# Sch2.net
KiCad netlist of a schematic drawn in Altium Designer
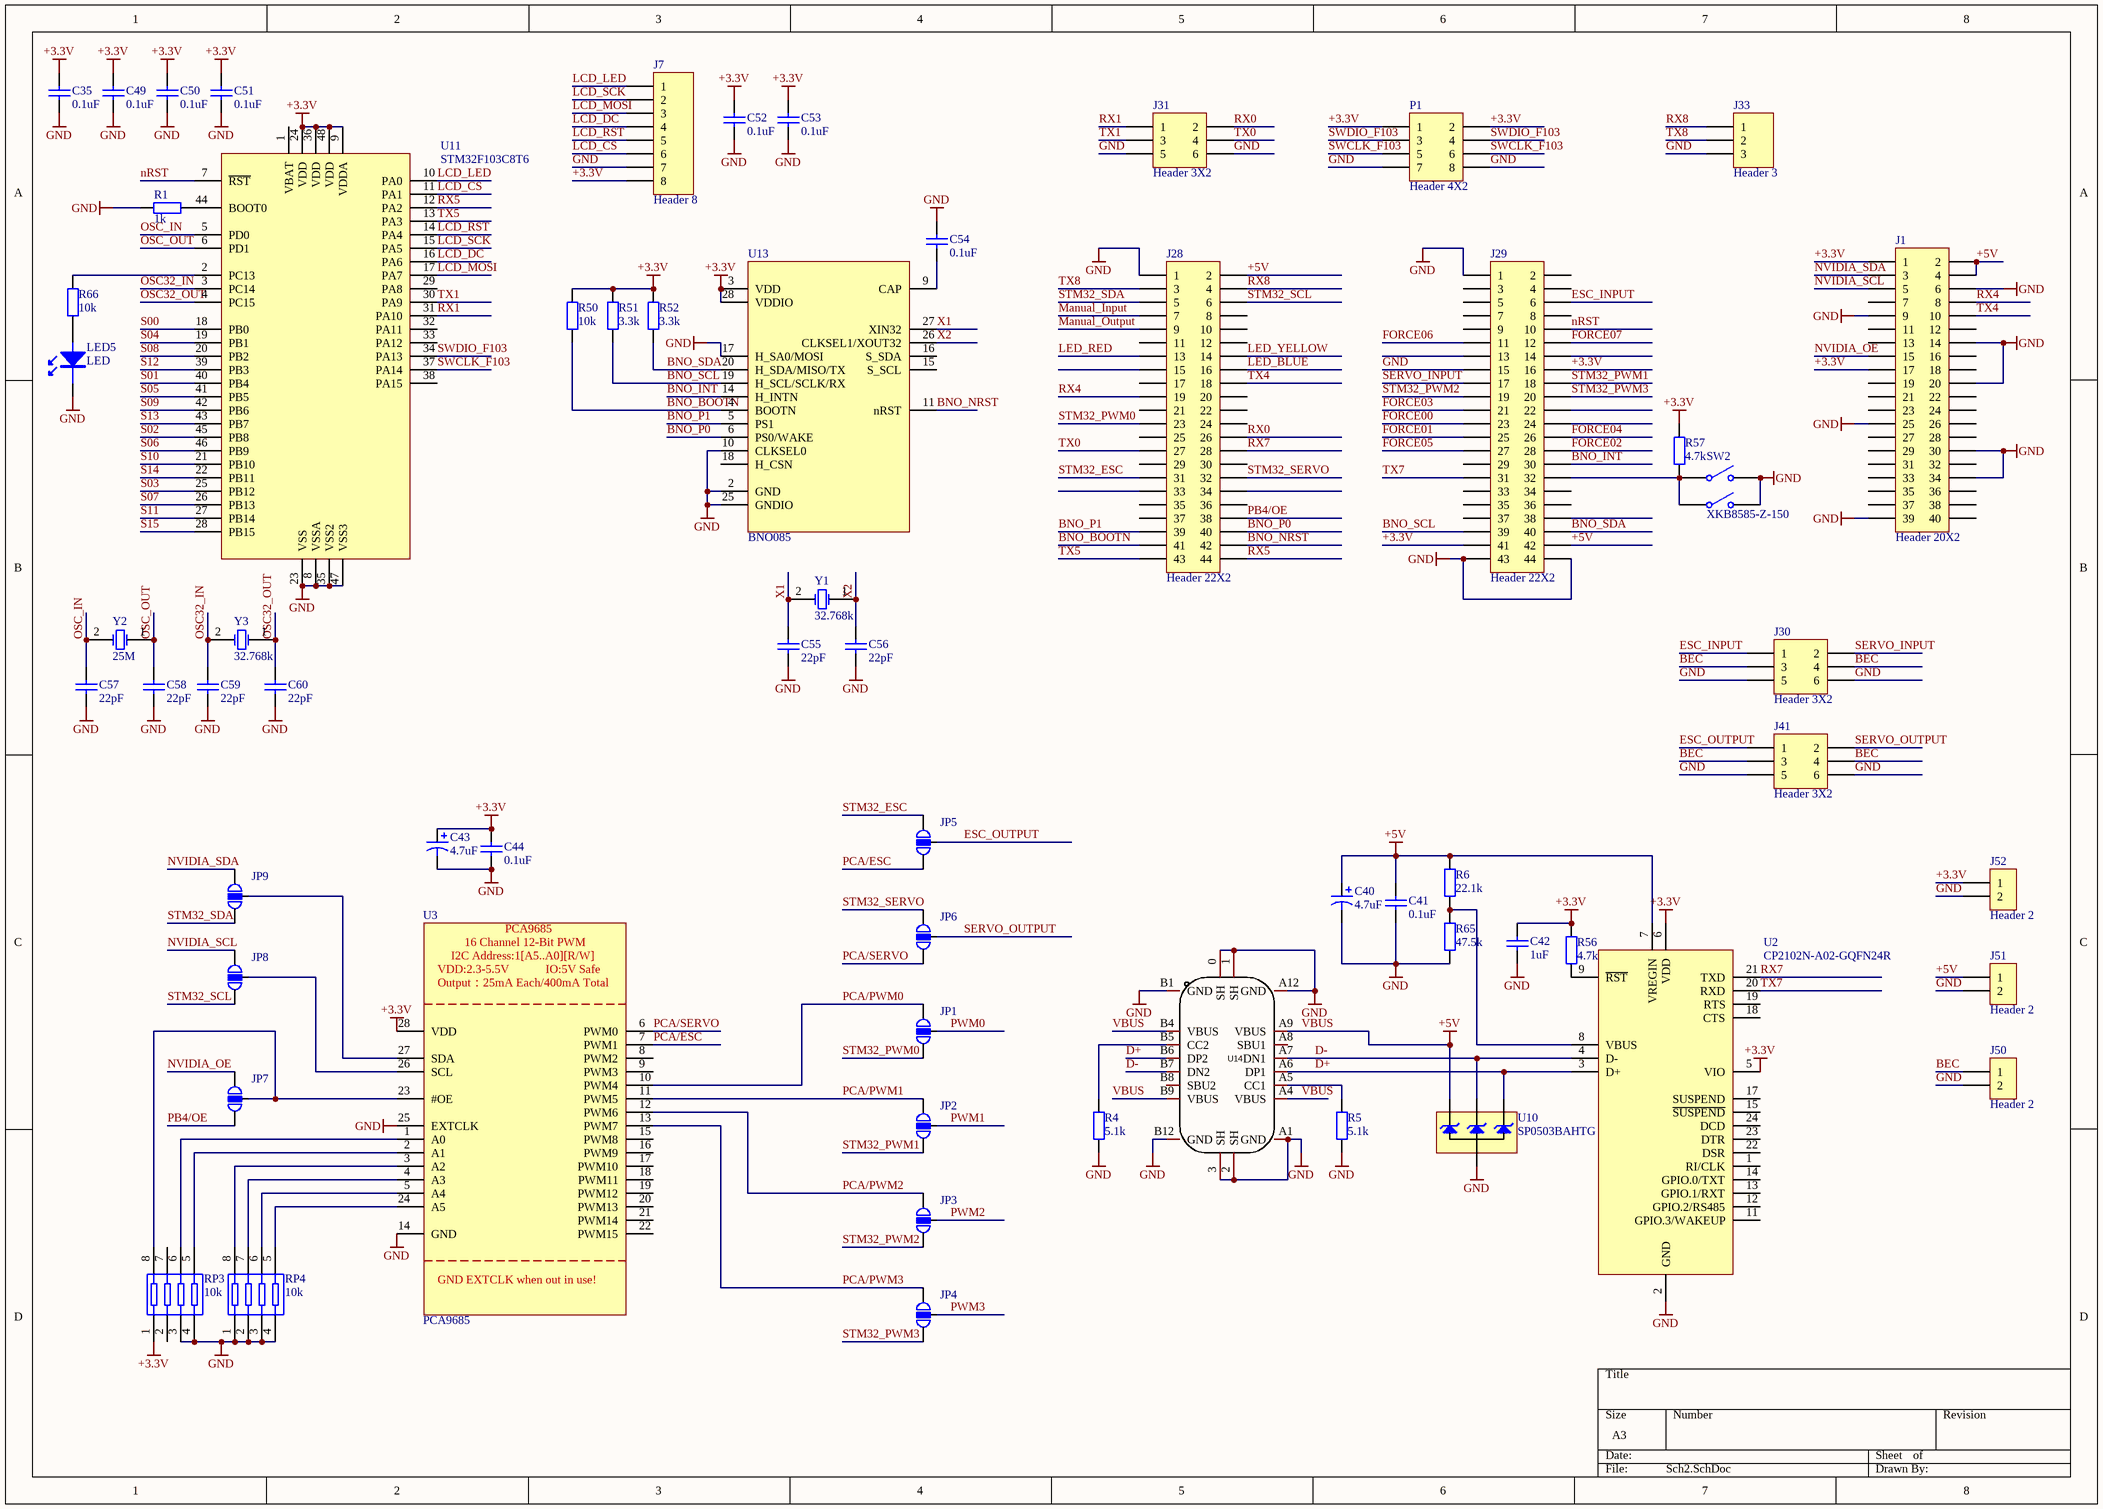
[diagram p0: Sch2.SchDoc]

(export (version "E")
  (design (tool "Eeschema 10.0.6"))
  (components
    (comp (ref "C35")
      (value "0.1uF")
      (footprint "CC0603")
      (description "贴片电容")
      (fields (field (name "Comment") "0603-50V-0.1uF"))
      (libsource (lib "Miscellaneous Devices") (part "Cap"))
    )
    (comp (ref "C40")
      (value "4.7uF")
      (footprint "SMD-EC-F5")
      (description "贴片铝电解电容")
      (fields (field (name "Comment") "CD-50V-4.7uF-F5(SMD)"))
      (libsource (lib "Miscellaneous Devices") (part "Cap Pol1"))
    )
    (comp (ref "C41")
      (value "0.1uF")
      (footprint "CC0603")
      (description "贴片电容")
      (fields (field (name "Comment") "0603-50V-0.1uF"))
      (libsource (lib "Miscellaneous Devices") (part "Cap"))
    )
    (comp (ref "C42")
      (value "1uF")
      (footprint "CC0603")
      (description "贴片电容")
      (fields (field (name "Comment") "0603-50V-1uF"))
      (libsource (lib "Miscellaneous Devices") (part "Cap"))
    )
    (comp (ref "C43")
      (value "4.7uF")
      (footprint "SMD-EC-F5")
      (description "贴片铝电解电容")
      (fields (field (name "Comment") "CD-50V-4.7uF-F5(SMD)"))
      (libsource (lib "Miscellaneous Devices") (part "Cap Pol1"))
    )
    (comp (ref "C44")
      (value "0.1uF")
      (footprint "CC0603")
      (description "贴片电容")
      (fields (field (name "Comment") "0603-50V-0.1uF"))
      (libsource (lib "Miscellaneous Devices") (part "Cap"))
    )
    (comp (ref "C49")
      (value "0.1uF")
      (footprint "CC0603")
      (description "贴片电容")
      (fields (field (name "Comment") "0603-50V-0.1uF"))
      (libsource (lib "Miscellaneous Devices") (part "Cap"))
    )
    (comp (ref "C50")
      (value "0.1uF")
      (footprint "CC0603")
      (description "贴片电容")
      (fields (field (name "Comment") "0603-50V-0.1uF"))
      (libsource (lib "Miscellaneous Devices") (part "Cap"))
    )
    (comp (ref "C51")
      (value "0.1uF")
      (footprint "CC0603")
      (description "贴片电容")
      (fields (field (name "Comment") "0603-50V-0.1uF"))
      (libsource (lib "Miscellaneous Devices") (part "Cap"))
    )
    (comp (ref "C52")
      (value "0.1uF")
      (footprint "CC0603")
      (description "贴片电容")
      (fields (field (name "Comment") "0603-50V-0.1uF"))
      (libsource (lib "Miscellaneous Devices") (part "Cap"))
    )
    (comp (ref "C53")
      (value "0.1uF")
      (footprint "CC0603")
      (description "贴片电容")
      (fields (field (name "Comment") "0603-50V-0.1uF"))
      (libsource (lib "Miscellaneous Devices") (part "Cap"))
    )
    (comp (ref "C54")
      (value "0.1uF")
      (footprint "CC0603")
      (description "贴片电容")
      (fields (field (name "Comment") "0603-50V-0.1uF"))
      (libsource (lib "Miscellaneous Devices") (part "Cap"))
    )
    (comp (ref "C55")
      (value "22pF")
      (footprint "CC0603")
      (description "贴片电容")
      (fields (field (name "Comment") "0603-50V-22pF"))
      (libsource (lib "Miscellaneous Devices") (part "Cap"))
    )
    (comp (ref "C56")
      (value "22pF")
      (footprint "CC0603")
      (description "贴片电容")
      (fields (field (name "Comment") "0603-50V-22pF"))
      (libsource (lib "Miscellaneous Devices") (part "Cap"))
    )
    (comp (ref "C57")
      (value "22pF")
      (footprint "CC0603")
      (description "贴片电容")
      (fields (field (name "Comment") "0603-50V-22pF"))
      (libsource (lib "Miscellaneous Devices") (part "Cap"))
    )
    (comp (ref "C58")
      (value "22pF")
      (footprint "CC0603")
      (description "贴片电容")
      (fields (field (name "Comment") "0603-50V-22pF"))
      (libsource (lib "Miscellaneous Devices") (part "Cap"))
    )
    (comp (ref "C59")
      (value "22pF")
      (footprint "CC0603")
      (description "贴片电容")
      (fields (field (name "Comment") "0603-50V-22pF"))
      (libsource (lib "Miscellaneous Devices") (part "Cap"))
    )
    (comp (ref "C60")
      (value "22pF")
      (footprint "CC0603")
      (description "贴片电容")
      (fields (field (name "Comment") "0603-50V-22pF"))
      (libsource (lib "Miscellaneous Devices") (part "Cap"))
    )
    (comp (ref "J1")
      (value "Header 20X2")
      (footprint "HDR2X20")
      (description "排针")
      (libsource (lib "Miscellaneous Connectors") (part "Header 20X2"))
    )
    (comp (ref "J7")
      (value "Header 8")
      (footprint "HDR1X8")
      (description "排针")
      (libsource (lib "Miscellaneous Connectors") (part "Header 8"))
    )
    (comp (ref "J28")
      (value "Header 22X2")
      (footprint "HDR2X22")
      (description "排针")
      (libsource (lib "Miscellaneous Connectors") (part "Header 22X2"))
    )
    (comp (ref "J29")
      (value "Header 22X2")
      (footprint "HDR2X22")
      (description "排针")
      (libsource (lib "Miscellaneous Connectors") (part "Header 22X2"))
    )
    (comp (ref "J30")
      (value "Header 3X2")
      (footprint "HDR2X3")
      (description "排针")
      (libsource (lib "Miscellaneous Connectors") (part "Header 3X2"))
    )
    (comp (ref "J31")
      (value "Header 3X2")
      (footprint "HDR2X3")
      (description "排针")
      (libsource (lib "Miscellaneous Connectors") (part "Header 3X2"))
    )
    (comp (ref "J33")
      (value "Header 3")
      (footprint "HDR1X3")
      (description "排针")
      (libsource (lib "Miscellaneous Connectors") (part "Header 3"))
    )
    (comp (ref "J41")
      (value "Header 3X2")
      (footprint "HDR2X3")
      (description "排针")
      (libsource (lib "Miscellaneous Connectors") (part "Header 3X2"))
    )
    (comp (ref "J50")
      (value "Header 2")
      (footprint "HDR1X2")
      (description "排针")
      (libsource (lib "*") (part "CON2"))
    )
    (comp (ref "J51")
      (value "Header 2")
      (footprint "HDR1X2")
      (description "排针")
      (libsource (lib "*") (part "CON2"))
    )
    (comp (ref "J52")
      (value "Header 2")
      (footprint "HDR1X2")
      (description "排针")
      (libsource (lib "*") (part "CON2"))
    )
    (comp (ref "JP1") (value "Jumper") (footprint "HDR1X3") (libsource (lib "SHIELD_3") (part "Bell")))
    (comp (ref "JP2") (value "Jumper") (footprint "HDR1X3") (libsource (lib "SHIELD_3") (part "Bell")))
    (comp (ref "JP3") (value "Jumper") (footprint "HDR1X3") (libsource (lib "SHIELD_3") (part "Bell")))
    (comp (ref "JP4") (value "Jumper") (footprint "HDR1X3") (libsource (lib "SHIELD_3") (part "Bell")))
    (comp (ref "JP5") (value "Jumper") (footprint "HDR1X3") (libsource (lib "SHIELD_3") (part "Bell")))
    (comp (ref "JP6") (value "Jumper") (footprint "HDR1X3") (libsource (lib "SHIELD_3") (part "Bell")))
    (comp (ref "JP7") (value "Jumper") (footprint "HDR1X3") (libsource (lib "SHIELD_3") (part "Bell")))
    (comp (ref "JP8") (value "Jumper") (footprint "HDR1X3") (libsource (lib "SHIELD_3") (part "Bell")))
    (comp (ref "JP9") (value "Jumper") (footprint "HDR1X3") (libsource (lib "SHIELD_3") (part "Bell")))
    (comp (ref "LED5")
      (value "LED")
      (footprint "LED0603")
      (description "发光二极管")
      (fields (field (name "Comment") "0603-LED-(蓝)"))
      (libsource (lib "*") (part "LED"))
    )
    (comp (ref "P1")
      (value "Header 4X2")
      (footprint "HDR2X4")
      (description "排针")
      (libsource (lib "Miscellaneous Connectors") (part "Header 4X2"))
    )
    (comp (ref "R1")
      (value "1k")
      (footprint "0603")
      (description "贴片电阻")
      (fields (field (name "Comment") "0603-1kΩ±1％"))
      (libsource (lib "") (part "Res2_2"))
    )
    (comp (ref "R4")
      (value "5.1k")
      (footprint "0603")
      (description "贴片电阻")
      (fields (field (name "Comment") "0603-5.1kΩ±1％"))
      (libsource (lib "") (part "Res2_1"))
    )
    (comp (ref "R5")
      (value "5.1k")
      (footprint "0603")
      (description "贴片电阻")
      (fields (field (name "Comment") "0603-5.1kΩ±1％"))
      (libsource (lib "") (part "Res2_1"))
    )
    (comp (ref "R6")
      (value "22.1k")
      (footprint "0603")
      (description "贴片电阻")
      (fields (field (name "Comment") "0603-22.1kΩ±1％"))
      (libsource (lib "Miscellaneous Devices") (part "Res2"))
    )
    (comp (ref "R50")
      (value "10k")
      (footprint "0603")
      (description "贴片电阻")
      (fields (field (name "Comment") "0603-10kΩ±1％"))
      (libsource (lib "") (part "Res2_1"))
    )
    (comp (ref "R51")
      (value "3.3k")
      (footprint "0603")
      (description "贴片电阻")
      (fields (field (name "Comment") "0603-3.3kΩ±1％"))
      (libsource (lib "") (part "Res2_1"))
    )
    (comp (ref "R52")
      (value "3.3k")
      (footprint "0603")
      (description "贴片电阻")
      (fields (field (name "Comment") "0603-3.3kΩ±1％"))
      (libsource (lib "") (part "Res2_1"))
    )
    (comp (ref "R56")
      (value "4.7k")
      (footprint "0603")
      (description "贴片电阻")
      (fields (field (name "Comment") "0603-4.7kΩ±1％"))
      (libsource (lib "Miscellaneous Devices") (part "Res2"))
    )
    (comp (ref "R57")
      (value "4.7k")
      (footprint "0603")
      (description "贴片电阻")
      (fields (field (name "Comment") "0603-4.7kΩ±1％"))
      (libsource (lib "Miscellaneous Devices") (part "Res2"))
    )
    (comp (ref "R65")
      (value "47.5k")
      (footprint "0603")
      (description "贴片电阻")
      (fields (field (name "Comment") "0603-47.5kΩ±1％"))
      (libsource (lib "Miscellaneous Devices") (part "Res2"))
    )
    (comp (ref "R66")
      (value "10k")
      (footprint "0603")
      (description "贴片电阻")
      (fields (field (name "Comment") "0603-10kΩ±1％"))
      (libsource (lib "") (part "Res2_1"))
    )
    (comp (ref "RP3")
      (value "10k")
      (footprint "RP8F")
      (description "排阻")
      (fields (field (name "Comment") "0603-10kΩ-2*4P"))
      (libsource (lib "*") (part "RESPACK8P"))
    )
    (comp (ref "RP4")
      (value "10k")
      (footprint "RP8F")
      (description "排阻")
      (fields (field (name "Comment") "0603-10kΩ-2*4P"))
      (libsource (lib "*") (part "RESPACK8P"))
    )
    (comp (ref "SW2")
      (value "XKB8585-Z-150")
      (footprint "KEY_SWITCH")
      (description "开关")
      (libsource (lib "PCB_Project") (part "SW-SPST"))
    )
    (comp (ref "U2")
      (value "CP2102N-A02-GQFN24R")
      (footprint "QFN24")
      (description "集成电路")
      (libsource (lib "PCB_Project") (part "CP2102N-A02-GQFN24R"))
    )
    (comp (ref "U3")
      (value "PCA9685")
      (footprint "LYDZ:TSSOP-28")
      (description "集成电路")
      (libsource (lib "Schlib1") (part "PCA9685"))
    )
    (comp (ref "U10")
      (value "SP0503BAHTG")
      (footprint "SOT143-4")
      (description "集成电路")
      (libsource (lib "PCB_Project") (part "SP0503BAHTG"))
    )
    (comp (ref "U11")
      (value "STM32F103C8T6")
      (footprint "LQFP48")
      (description "集成电路")
      (libsource (lib "Schlib2") (part "STM32F103C8T6"))
    )
    (comp (ref "U13")
      (value "BNO085")
      (footprint "LGA28")
      (description "集成电路")
      (libsource (lib "Schlib1") (part "BNO080"))
    )
    (comp (ref "U14")
      (value "TYPE-C-31-M-12")
      (footprint "USB-C_SMD-TYPE-C-31-M-12")
      (fields (field (name "MANUFACTURER") "韩国韩荣"))
      (libsource (lib "altium-import") (part "root_0_TYPE-C-31-M-12_"))
    )
    (comp (ref "Y1")
      (value "32.768k")
      (footprint "XTAL-FA135")
      (description "Crystal Oscillator")
      (fields (field (name "PUBLISHER") "Altium Limited"))
      (libsource (lib "Miscellaneous Devices") (part "XTAL"))
    )
    (comp (ref "Y2")
      (value "25M")
      (footprint "XT49M")
      (description "Crystal Oscillator")
      (fields (field (name "PUBLISHER") "Altium Limited"))
      (libsource (lib "Miscellaneous Devices") (part "XTAL"))
    )
    (comp (ref "Y3")
      (value "32.768k")
      (footprint "XTAL-FA135")
      (description "Crystal Oscillator")
      (fields (field (name "PUBLISHER") "Altium Limited"))
      (libsource (lib "Miscellaneous Devices") (part "XTAL"))
    )
  )
  (nets
    (net (code "1") (name "+3.3V") (class "Default")
      (node (ref "C35") (pin "2") (pinfunction "2_2") (pintype "passive"))
      (node (ref "C42") (pin "2") (pinfunction "2_2") (pintype "passive"))
      (node (ref "C43") (pin "1") (pinfunction "1_1") (pintype "passive"))
      (node (ref "C44") (pin "2") (pinfunction "2_2") (pintype "passive"))
      (node (ref "C49") (pin "2") (pinfunction "2_2") (pintype "passive"))
      (node (ref "C50") (pin "2") (pinfunction "2_2") (pintype "passive"))
      (node (ref "C51") (pin "2") (pinfunction "2_2") (pintype "passive"))
      (node (ref "C52") (pin "2") (pinfunction "2_2") (pintype "passive"))
      (node (ref "C53") (pin "2") (pinfunction "2_2") (pintype "passive"))
      (node (ref "J1") (pin "1") (pinfunction "1_1") (pintype "passive"))
      (node (ref "J1") (pin "17") (pinfunction "17_17") (pintype "passive"))
      (node (ref "J29") (pin "16") (pinfunction "16_16") (pintype "passive"))
      (node (ref "J29") (pin "41") (pinfunction "41_41") (pintype "passive"))
      (node (ref "J52") (pin "1") (pinfunction "1_1") (pintype "passive"))
      (node (ref "J7") (pin "8") (pinfunction "8_8") (pintype "passive"))
      (node (ref "P1") (pin "1") (pinfunction "1_1") (pintype "passive"))
      (node (ref "P1") (pin "2") (pinfunction "2_2") (pintype "passive"))
      (node (ref "R50") (pin "2") (pinfunction "2_2") (pintype "passive"))
      (node (ref "R51") (pin "2") (pinfunction "2_2") (pintype "passive"))
      (node (ref "R52") (pin "2") (pinfunction "2_2") (pintype "passive"))
      (node (ref "R56") (pin "1") (pinfunction "1_1") (pintype "passive"))
      (node (ref "R57") (pin "1") (pinfunction "1_1") (pintype "passive"))
      (node (ref "RP3") (pin "1") (pinfunction "1_1") (pintype "passive"))
      (node (ref "U11") (pin "24") (pinfunction "VDD_24") (pintype "passive"))
      (node (ref "U11") (pin "36") (pinfunction "VDD_36") (pintype "passive"))
      (node (ref "U11") (pin "48") (pinfunction "VDD_48") (pintype "passive"))
      (node (ref "U11") (pin "9") (pinfunction "VDDA_9") (pintype "passive"))
      (node (ref "U13") (pin "28") (pinfunction "VDDIO_28") (pintype "passive"))
      (node (ref "U13") (pin "3") (pinfunction "VDD_3") (pintype "passive"))
      (node (ref "U2") (pin "5") (pinfunction "VIO_5") (pintype "passive"))
      (node (ref "U2") (pin "6") (pinfunction "VDD_6") (pintype "passive"))
      (node (ref "U3") (pin "28") (pinfunction "VDD_28") (pintype "passive"))
    )
    (net (code "2") (name "+5V") (class "Default")
      (node (ref "C40") (pin "1") (pinfunction "1_1") (pintype "passive"))
      (node (ref "C41") (pin "2") (pinfunction "2_2") (pintype "passive"))
      (node (ref "J1") (pin "2") (pinfunction "2_2") (pintype "passive"))
      (node (ref "J1") (pin "4") (pinfunction "4_4") (pintype "passive"))
      (node (ref "J28") (pin "2") (pinfunction "2_2") (pintype "passive"))
      (node (ref "J29") (pin "42") (pinfunction "42_42") (pintype "passive"))
      (node (ref "J51") (pin "1") (pinfunction "1_1") (pintype "passive"))
      (node (ref "R6") (pin "1") (pinfunction "1_1") (pintype "passive"))
      (node (ref "U10") (pin "2") (pinfunction "K_2") (pintype "passive"))
      (node (ref "U14") (pin "A4") (pinfunction "VBUS_A4") (pintype "passive"))
      (node (ref "U14") (pin "A9") (pinfunction "VBUS_A9") (pintype "passive"))
      (node (ref "U14") (pin "B4") (pinfunction "VBUS_B4") (pintype "passive"))
      (node (ref "U14") (pin "B9") (pinfunction "VBUS_B9") (pintype "passive"))
      (node (ref "U2") (pin "7") (pinfunction "VREGIN_7") (pintype "passive"))
    )
    (net (code "3") (name "/BEC") (class "Default")
      (node (ref "J30") (pin "3") (pinfunction "3_3") (pintype "passive"))
      (node (ref "J30") (pin "4") (pinfunction "4_4") (pintype "passive"))
      (node (ref "J41") (pin "3") (pinfunction "3_3") (pintype "passive"))
      (node (ref "J41") (pin "4") (pinfunction "4_4") (pintype "passive"))
      (node (ref "J50") (pin "1") (pinfunction "1_1") (pintype "passive"))
    )
    (net (code "4") (name "/BNO_BOOTN") (class "Default")
      (node (ref "J28") (pin "41") (pinfunction "41_41") (pintype "passive"))
      (node (ref "R50") (pin "1") (pinfunction "1_1") (pintype "passive"))
      (node (ref "U13") (pin "4") (pinfunction "BOOTN_4") (pintype "passive"))
    )
    (net (code "5") (name "/BNO_INT") (class "Default")
      (node (ref "J29") (pin "30") (pinfunction "30_30") (pintype "passive"))
      (node (ref "U13") (pin "14") (pinfunction "H_INTN_14") (pintype "passive"))
    )
    (net (code "6") (name "/BNO_NRST") (class "Default")
      (node (ref "J28") (pin "42") (pinfunction "42_42") (pintype "passive"))
      (node (ref "U13") (pin "11") (pinfunction "nRST_11") (pintype "passive"))
    )
    (net (code "7") (name "/BNO_P0") (class "Default")
      (node (ref "J28") (pin "40") (pinfunction "40_40") (pintype "passive"))
      (node (ref "U13") (pin "6") (pinfunction "PS0/WAKE_6") (pintype "passive"))
    )
    (net (code "8") (name "/BNO_P1") (class "Default")
      (node (ref "J28") (pin "39") (pinfunction "39_39") (pintype "passive"))
      (node (ref "U13") (pin "5") (pinfunction "PS1_5") (pintype "passive"))
    )
    (net (code "9") (name "/BNO_SCL") (class "Default")
      (node (ref "J29") (pin "39") (pinfunction "39_39") (pintype "passive"))
      (node (ref "R51") (pin "1") (pinfunction "1_1") (pintype "passive"))
      (node (ref "U13") (pin "19") (pinfunction "H_SCL/SCLK/RX_19") (pintype "passive"))
    )
    (net (code "10") (name "/BNO_SDA") (class "Default")
      (node (ref "J29") (pin "40") (pinfunction "40_40") (pintype "passive"))
      (node (ref "R52") (pin "1") (pinfunction "1_1") (pintype "passive"))
      (node (ref "U13") (pin "20") (pinfunction "H_SDA/MISO/TX_20") (pintype "passive"))
    )
    (net (code "11") (name "/D+") (class "Default")
      (node (ref "U10") (pin "4") (pinfunction "K_4") (pintype "passive"))
      (node (ref "U14") (pin "A6") (pinfunction "DP1_A6") (pintype "passive"))
      (node (ref "U14") (pin "B6") (pinfunction "DP2_B6") (pintype "passive"))
      (node (ref "U2") (pin "3") (pinfunction "D+_3") (pintype "passive"))
    )
    (net (code "12") (name "/D-") (class "Default")
      (node (ref "U10") (pin "3") (pinfunction "K_3") (pintype "passive"))
      (node (ref "U14") (pin "A7") (pinfunction "DN1_A7") (pintype "passive"))
      (node (ref "U14") (pin "B7") (pinfunction "DN2_B7") (pintype "passive"))
      (node (ref "U2") (pin "4") (pinfunction "D-_4") (pintype "passive"))
    )
    (net (code "13") (name "/ESC_INPUT") (class "Default")
      (node (ref "J29") (pin "6") (pinfunction "6_6") (pintype "passive"))
      (node (ref "J30") (pin "1") (pinfunction "1_1") (pintype "passive"))
    )
    (net (code "14") (name "/ESC_OUTPUT") (class "Default")
      (node (ref "J41") (pin "1") (pinfunction "1_1") (pintype "passive"))
      (node (ref "JP5") (pin "2") (pinfunction "B_2") (pintype "passive"))
    )
    (net (code "15") (name "/FORCE00") (class "Default")
      (node (ref "J29") (pin "23") (pinfunction "23_23") (pintype "passive"))
    )
    (net (code "16") (name "/FORCE01") (class "Default")
      (node (ref "J29") (pin "25") (pinfunction "25_25") (pintype "passive"))
    )
    (net (code "17") (name "/FORCE02") (class "Default")
      (node (ref "J29") (pin "28") (pinfunction "28_28") (pintype "passive"))
    )
    (net (code "18") (name "/FORCE03") (class "Default")
      (node (ref "J29") (pin "21") (pinfunction "21_21") (pintype "passive"))
    )
    (net (code "19") (name "/FORCE04") (class "Default")
      (node (ref "J29") (pin "26") (pinfunction "26_26") (pintype "passive"))
    )
    (net (code "20") (name "/FORCE05") (class "Default")
      (node (ref "J29") (pin "27") (pinfunction "27_27") (pintype "passive"))
    )
    (net (code "21") (name "/FORCE06") (class "Default")
      (node (ref "J29") (pin "11") (pinfunction "11_11") (pintype "passive"))
    )
    (net (code "22") (name "/FORCE07") (class "Default")
      (node (ref "J29") (pin "12") (pinfunction "12_12") (pintype "passive"))
    )
    (net (code "23") (name "/LCD_CS") (class "Default")
      (node (ref "J7") (pin "6") (pinfunction "6_6") (pintype "passive"))
      (node (ref "U11") (pin "11") (pinfunction "PA1_11") (pintype "passive"))
    )
    (net (code "24") (name "/LCD_DC") (class "Default")
      (node (ref "J7") (pin "4") (pinfunction "4_4") (pintype "passive"))
      (node (ref "U11") (pin "16") (pinfunction "PA6_16") (pintype "passive"))
    )
    (net (code "25") (name "/LCD_LED") (class "Default")
      (node (ref "J7") (pin "1") (pinfunction "1_1") (pintype "passive"))
      (node (ref "U11") (pin "10") (pinfunction "PA0_10") (pintype "passive"))
    )
    (net (code "26") (name "/LCD_MOSI") (class "Default")
      (node (ref "J7") (pin "3") (pinfunction "3_3") (pintype "passive"))
      (node (ref "U11") (pin "17") (pinfunction "PA7_17") (pintype "passive"))
    )
    (net (code "27") (name "/LCD_RST") (class "Default")
      (node (ref "J7") (pin "5") (pinfunction "5_5") (pintype "passive"))
      (node (ref "U11") (pin "14") (pinfunction "PA4_14") (pintype "passive"))
    )
    (net (code "28") (name "/LCD_SCK") (class "Default")
      (node (ref "J7") (pin "2") (pinfunction "2_2") (pintype "passive"))
      (node (ref "U11") (pin "15") (pinfunction "PA5_15") (pintype "passive"))
    )
    (net (code "29") (name "/LED_BLUE") (class "Default")
      (node (ref "J28") (pin "16") (pinfunction "16_16") (pintype "passive"))
    )
    (net (code "30") (name "/LED_RED") (class "Default")
      (node (ref "J28") (pin "13") (pinfunction "13_13") (pintype "passive"))
    )
    (net (code "31") (name "/LED_YELLOW") (class "Default")
      (node (ref "J28") (pin "14") (pinfunction "14_14") (pintype "passive"))
    )
    (net (code "32") (name "/Manual_Input") (class "Default")
      (node (ref "J28") (pin "7") (pinfunction "7_7") (pintype "passive"))
    )
    (net (code "33") (name "/Manual_Output") (class "Default")
      (node (ref "J28") (pin "9") (pinfunction "9_9") (pintype "passive"))
    )
    (net (code "34") (name "/NVIDIA_OE") (class "Default")
      (node (ref "J1") (pin "15") (pinfunction "15_15") (pintype "passive"))
      (node (ref "JP7") (pin "1") (pinfunction "A_1") (pintype "passive"))
    )
    (net (code "35") (name "/NVIDIA_SCL") (class "Default")
      (node (ref "J1") (pin "5") (pinfunction "5_5") (pintype "passive"))
      (node (ref "JP8") (pin "1") (pinfunction "A_1") (pintype "passive"))
    )
    (net (code "36") (name "/NVIDIA_SDA") (class "Default")
      (node (ref "J1") (pin "3") (pinfunction "3_3") (pintype "passive"))
      (node (ref "JP9") (pin "1") (pinfunction "A_1") (pintype "passive"))
    )
    (net (code "37") (name "/OSC32_IN") (class "Default")
      (node (ref "C59") (pin "1") (pinfunction "1_1") (pintype "passive"))
      (node (ref "U11") (pin "3") (pinfunction "PC14_3") (pintype "passive"))
      (node (ref "Y3") (pin "2") (pinfunction "OSC2_2") (pintype "passive"))
    )
    (net (code "38") (name "/OSC32_OUT") (class "Default")
      (node (ref "C60") (pin "1") (pinfunction "1_1") (pintype "passive"))
      (node (ref "U11") (pin "4") (pinfunction "PC15_4") (pintype "passive"))
      (node (ref "Y3") (pin "1") (pinfunction "OSC1_1") (pintype "passive"))
    )
    (net (code "39") (name "/OSC_IN") (class "Default")
      (node (ref "C57") (pin "1") (pinfunction "1_1") (pintype "passive"))
      (node (ref "U11") (pin "5") (pinfunction "PD0_5") (pintype "passive"))
      (node (ref "Y2") (pin "2") (pinfunction "OSC2_2") (pintype "passive"))
    )
    (net (code "40") (name "/OSC_OUT") (class "Default")
      (node (ref "C58") (pin "1") (pinfunction "1_1") (pintype "passive"))
      (node (ref "U11") (pin "6") (pinfunction "PD1_6") (pintype "passive"))
      (node (ref "Y2") (pin "1") (pinfunction "OSC1_1") (pintype "passive"))
    )
    (net (code "41") (name "/PB4{slash}OE") (class "Default")
      (node (ref "J28") (pin "38") (pinfunction "38_38") (pintype "passive"))
      (node (ref "JP7") (pin "3") (pinfunction "B_3") (pintype "passive"))
    )
    (net (code "42") (name "/PCA{slash}ESC") (class "Default")
      (node (ref "JP5") (pin "3") (pinfunction "B_3") (pintype "passive"))
      (node (ref "U3") (pin "7") (pinfunction "PWM1_7") (pintype "passive"))
    )
    (net (code "43") (name "/PCA{slash}PWM0") (class "Default")
      (node (ref "JP1") (pin "1") (pinfunction "A_1") (pintype "passive"))
      (node (ref "U3") (pin "10") (pinfunction "PWM4_10") (pintype "passive"))
    )
    (net (code "44") (name "/PCA{slash}PWM1") (class "Default")
      (node (ref "JP2") (pin "1") (pinfunction "A_1") (pintype "passive"))
      (node (ref "U3") (pin "11") (pinfunction "PWM5_11") (pintype "passive"))
    )
    (net (code "45") (name "/PCA{slash}PWM2") (class "Default")
      (node (ref "JP3") (pin "1") (pinfunction "A_1") (pintype "passive"))
      (node (ref "U3") (pin "12") (pinfunction "PWM6_12") (pintype "passive"))
    )
    (net (code "46") (name "/PCA{slash}PWM3") (class "Default")
      (node (ref "JP4") (pin "1") (pinfunction "A_1") (pintype "passive"))
      (node (ref "U3") (pin "13") (pinfunction "PWM7_13") (pintype "passive"))
    )
    (net (code "47") (name "/PCA{slash}SERVO") (class "Default")
      (node (ref "JP6") (pin "3") (pinfunction "B_3") (pintype "passive"))
      (node (ref "U3") (pin "6") (pinfunction "PWM0_6") (pintype "passive"))
    )
    (net (code "48") (name "/PWM0") (class "Default")
      (node (ref "JP1") (pin "2") (pinfunction "B_2") (pintype "passive"))
    )
    (net (code "49") (name "/PWM1") (class "Default")
      (node (ref "JP2") (pin "2") (pinfunction "B_2") (pintype "passive"))
    )
    (net (code "50") (name "/PWM2") (class "Default")
      (node (ref "JP3") (pin "2") (pinfunction "B_2") (pintype "passive"))
    )
    (net (code "51") (name "/PWM3") (class "Default")
      (node (ref "JP4") (pin "2") (pinfunction "B_2") (pintype "passive"))
    )
    (net (code "52") (name "/RX0") (class "Default")
      (node (ref "J28") (pin "26") (pinfunction "26_26") (pintype "passive"))
      (node (ref "J31") (pin "2") (pinfunction "2_2") (pintype "passive"))
    )
    (net (code "53") (name "/RX1") (class "Default")
      (node (ref "J31") (pin "1") (pinfunction "1_1") (pintype "passive"))
      (node (ref "U11") (pin "31") (pinfunction "PA10_31") (pintype "passive"))
    )
    (net (code "54") (name "/RX4") (class "Default")
      (node (ref "J1") (pin "8") (pinfunction "8_8") (pintype "passive"))
      (node (ref "J28") (pin "19") (pinfunction "19_19") (pintype "passive"))
    )
    (net (code "55") (name "/RX5") (class "Default")
      (node (ref "J28") (pin "44") (pinfunction "44_44") (pintype "passive"))
      (node (ref "U11") (pin "12") (pinfunction "PA2_12") (pintype "passive"))
    )
    (net (code "56") (name "/RX7") (class "Default")
      (node (ref "J28") (pin "28") (pinfunction "28_28") (pintype "passive"))
      (node (ref "U2") (pin "21") (pinfunction "TXD_21") (pintype "passive"))
    )
    (net (code "57") (name "/RX8") (class "Default")
      (node (ref "J28") (pin "4") (pinfunction "4_4") (pintype "passive"))
      (node (ref "J33") (pin "1") (pinfunction "1_1") (pintype "passive"))
    )
    (net (code "58") (name "/S00") (class "Default")
      (node (ref "U11") (pin "18") (pinfunction "PB0_18") (pintype "passive"))
    )
    (net (code "59") (name "/S01") (class "Default")
      (node (ref "U11") (pin "40") (pinfunction "PB4_40") (pintype "passive"))
    )
    (net (code "60") (name "/S02") (class "Default")
      (node (ref "U11") (pin "45") (pinfunction "PB8_45") (pintype "passive"))
    )
    (net (code "61") (name "/S03") (class "Default")
      (node (ref "U11") (pin "25") (pinfunction "PB12_25") (pintype "passive"))
    )
    (net (code "62") (name "/S04") (class "Default")
      (node (ref "U11") (pin "19") (pinfunction "PB1_19") (pintype "passive"))
    )
    (net (code "63") (name "/S05") (class "Default")
      (node (ref "U11") (pin "41") (pinfunction "PB5_41") (pintype "passive"))
    )
    (net (code "64") (name "/S06") (class "Default")
      (node (ref "U11") (pin "46") (pinfunction "PB9_46") (pintype "passive"))
    )
    (net (code "65") (name "/S07") (class "Default")
      (node (ref "U11") (pin "26") (pinfunction "PB13_26") (pintype "passive"))
    )
    (net (code "66") (name "/S08") (class "Default")
      (node (ref "U11") (pin "20") (pinfunction "PB2_20") (pintype "passive"))
    )
    (net (code "67") (name "/S09") (class "Default")
      (node (ref "U11") (pin "42") (pinfunction "PB6_42") (pintype "passive"))
    )
    (net (code "68") (name "/S10") (class "Default")
      (node (ref "U11") (pin "21") (pinfunction "PB10_21") (pintype "passive"))
    )
    (net (code "69") (name "/S11") (class "Default")
      (node (ref "U11") (pin "27") (pinfunction "PB14_27") (pintype "passive"))
    )
    (net (code "70") (name "/S12") (class "Default")
      (node (ref "U11") (pin "39") (pinfunction "PB3_39") (pintype "passive"))
    )
    (net (code "71") (name "/S13") (class "Default")
      (node (ref "U11") (pin "43") (pinfunction "PB7_43") (pintype "passive"))
    )
    (net (code "72") (name "/S14") (class "Default")
      (node (ref "U11") (pin "22") (pinfunction "PB11_22") (pintype "passive"))
    )
    (net (code "73") (name "/S15") (class "Default")
      (node (ref "U11") (pin "28") (pinfunction "PB15_28") (pintype "passive"))
    )
    (net (code "74") (name "/SERVO_INPUT") (class "Default")
      (node (ref "J29") (pin "17") (pinfunction "17_17") (pintype "passive"))
      (node (ref "J30") (pin "2") (pinfunction "2_2") (pintype "passive"))
    )
    (net (code "75") (name "/SERVO_OUTPUT") (class "Default")
      (node (ref "J41") (pin "2") (pinfunction "2_2") (pintype "passive"))
      (node (ref "JP6") (pin "2") (pinfunction "B_2") (pintype "passive"))
    )
    (net (code "76") (name "/STM32_ESC") (class "Default")
      (node (ref "J28") (pin "31") (pinfunction "31_31") (pintype "passive"))
      (node (ref "JP5") (pin "1") (pinfunction "A_1") (pintype "passive"))
    )
    (net (code "77") (name "/STM32_PWM0") (class "Default")
      (node (ref "J28") (pin "23") (pinfunction "23_23") (pintype "passive"))
      (node (ref "JP1") (pin "3") (pinfunction "B_3") (pintype "passive"))
    )
    (net (code "78") (name "/STM32_PWM1") (class "Default")
      (node (ref "J29") (pin "18") (pinfunction "18_18") (pintype "passive"))
      (node (ref "JP2") (pin "3") (pinfunction "B_3") (pintype "passive"))
    )
    (net (code "79") (name "/STM32_PWM2") (class "Default")
      (node (ref "J29") (pin "19") (pinfunction "19_19") (pintype "passive"))
      (node (ref "JP3") (pin "3") (pinfunction "B_3") (pintype "passive"))
    )
    (net (code "80") (name "/STM32_PWM3") (class "Default")
      (node (ref "J29") (pin "20") (pinfunction "20_20") (pintype "passive"))
      (node (ref "JP4") (pin "3") (pinfunction "B_3") (pintype "passive"))
    )
    (net (code "81") (name "/STM32_SCL") (class "Default")
      (node (ref "J28") (pin "6") (pinfunction "6_6") (pintype "passive"))
      (node (ref "JP8") (pin "3") (pinfunction "B_3") (pintype "passive"))
    )
    (net (code "82") (name "/STM32_SDA") (class "Default")
      (node (ref "J28") (pin "5") (pinfunction "5_5") (pintype "passive"))
      (node (ref "JP9") (pin "3") (pinfunction "B_3") (pintype "passive"))
    )
    (net (code "83") (name "/STM32_SERVO") (class "Default")
      (node (ref "J28") (pin "32") (pinfunction "32_32") (pintype "passive"))
      (node (ref "JP6") (pin "1") (pinfunction "A_1") (pintype "passive"))
    )
    (net (code "84") (name "/SWCLK_F103") (class "Default")
      (node (ref "P1") (pin "5") (pinfunction "5_5") (pintype "passive"))
      (node (ref "P1") (pin "6") (pinfunction "6_6") (pintype "passive"))
      (node (ref "U11") (pin "37") (pinfunction "PA14_37") (pintype "passive"))
    )
    (net (code "85") (name "/SWDIO_F103") (class "Default")
      (node (ref "P1") (pin "3") (pinfunction "3_3") (pintype "passive"))
      (node (ref "P1") (pin "4") (pinfunction "4_4") (pintype "passive"))
      (node (ref "U11") (pin "34") (pinfunction "PA13_34") (pintype "passive"))
    )
    (net (code "86") (name "/TX0") (class "Default")
      (node (ref "J28") (pin "27") (pinfunction "27_27") (pintype "passive"))
      (node (ref "J31") (pin "4") (pinfunction "4_4") (pintype "passive"))
    )
    (net (code "87") (name "/TX1") (class "Default")
      (node (ref "J31") (pin "3") (pinfunction "3_3") (pintype "passive"))
      (node (ref "U11") (pin "30") (pinfunction "PA9_30") (pintype "passive"))
    )
    (net (code "88") (name "/TX4") (class "Default")
      (node (ref "J1") (pin "10") (pinfunction "10_10") (pintype "passive"))
      (node (ref "J28") (pin "18") (pinfunction "18_18") (pintype "passive"))
    )
    (net (code "89") (name "/TX5") (class "Default")
      (node (ref "J28") (pin "43") (pinfunction "43_43") (pintype "passive"))
      (node (ref "U11") (pin "13") (pinfunction "PA3_13") (pintype "passive"))
    )
    (net (code "90") (name "/TX7") (class "Default")
      (node (ref "J29") (pin "31") (pinfunction "31_31") (pintype "passive"))
      (node (ref "U2") (pin "20") (pinfunction "RXD_20") (pintype "passive"))
    )
    (net (code "91") (name "/TX8") (class "Default")
      (node (ref "J28") (pin "3") (pinfunction "3_3") (pintype "passive"))
      (node (ref "J33") (pin "2") (pinfunction "2_2") (pintype "passive"))
    )
    (net (code "92") (name "/X1") (class "Default")
      (node (ref "C55") (pin "1") (pinfunction "1_1") (pintype "passive"))
      (node (ref "U13") (pin "27") (pinfunction "XIN32_27") (pintype "passive"))
      (node (ref "Y1") (pin "2") (pinfunction "OSC2_2") (pintype "passive"))
    )
    (net (code "93") (name "/X2") (class "Default")
      (node (ref "C56") (pin "1") (pinfunction "1_1") (pintype "passive"))
      (node (ref "U13") (pin "26") (pinfunction "CLKSEL1/XOUT32_26") (pintype "passive"))
      (node (ref "Y1") (pin "1") (pinfunction "OSC1_1") (pintype "passive"))
    )
    (net (code "94") (name "/nRST") (class "Default")
      (node (ref "J29") (pin "10") (pinfunction "10_10") (pintype "passive"))
      (node (ref "U11") (pin "7") (pinfunction "~{RST}_7") (pintype "passive"))
    )
    (net (code "95") (name "GND") (class "Default")
      (node (ref "C35") (pin "1") (pinfunction "1_1") (pintype "passive"))
      (node (ref "C40") (pin "2") (pinfunction "2_2") (pintype "passive"))
      (node (ref "C41") (pin "1") (pinfunction "1_1") (pintype "passive"))
      (node (ref "C42") (pin "1") (pinfunction "1_1") (pintype "passive"))
      (node (ref "C43") (pin "2") (pinfunction "2_2") (pintype "passive"))
      (node (ref "C44") (pin "1") (pinfunction "1_1") (pintype "passive"))
      (node (ref "C49") (pin "1") (pinfunction "1_1") (pintype "passive"))
      (node (ref "C50") (pin "1") (pinfunction "1_1") (pintype "passive"))
      (node (ref "C51") (pin "1") (pinfunction "1_1") (pintype "passive"))
      (node (ref "C52") (pin "1") (pinfunction "1_1") (pintype "passive"))
      (node (ref "C53") (pin "1") (pinfunction "1_1") (pintype "passive"))
      (node (ref "C54") (pin "2") (pinfunction "2_2") (pintype "passive"))
      (node (ref "C55") (pin "2") (pinfunction "2_2") (pintype "passive"))
      (node (ref "C56") (pin "2") (pinfunction "2_2") (pintype "passive"))
      (node (ref "C57") (pin "2") (pinfunction "2_2") (pintype "passive"))
      (node (ref "C58") (pin "2") (pinfunction "2_2") (pintype "passive"))
      (node (ref "C59") (pin "2") (pinfunction "2_2") (pintype "passive"))
      (node (ref "C60") (pin "2") (pinfunction "2_2") (pintype "passive"))
      (node (ref "J1") (pin "14") (pinfunction "14_14") (pintype "passive"))
      (node (ref "J1") (pin "20") (pinfunction "20_20") (pintype "passive"))
      (node (ref "J1") (pin "25") (pinfunction "25_25") (pintype "passive"))
      (node (ref "J1") (pin "30") (pinfunction "30_30") (pintype "passive"))
      (node (ref "J1") (pin "34") (pinfunction "34_34") (pintype "passive"))
      (node (ref "J1") (pin "39") (pinfunction "39_39") (pintype "passive"))
      (node (ref "J1") (pin "6") (pinfunction "6_6") (pintype "passive"))
      (node (ref "J1") (pin "9") (pinfunction "9_9") (pintype "passive"))
      (node (ref "J28") (pin "1") (pinfunction "1_1") (pintype "passive"))
      (node (ref "J29") (pin "1") (pinfunction "1_1") (pintype "passive"))
      (node (ref "J29") (pin "15") (pinfunction "15_15") (pintype "passive"))
      (node (ref "J29") (pin "43") (pinfunction "43_43") (pintype "passive"))
      (node (ref "J29") (pin "44") (pinfunction "44_44") (pintype "passive"))
      (node (ref "J30") (pin "5") (pinfunction "5_5") (pintype "passive"))
      (node (ref "J30") (pin "6") (pinfunction "6_6") (pintype "passive"))
      (node (ref "J31") (pin "5") (pinfunction "5_5") (pintype "passive"))
      (node (ref "J31") (pin "6") (pinfunction "6_6") (pintype "passive"))
      (node (ref "J33") (pin "3") (pinfunction "3_3") (pintype "passive"))
      (node (ref "J41") (pin "5") (pinfunction "5_5") (pintype "passive"))
      (node (ref "J41") (pin "6") (pinfunction "6_6") (pintype "passive"))
      (node (ref "J50") (pin "2") (pinfunction "2_2") (pintype "passive"))
      (node (ref "J51") (pin "2") (pinfunction "2_2") (pintype "passive"))
      (node (ref "J52") (pin "2") (pinfunction "2_2") (pintype "passive"))
      (node (ref "J7") (pin "7") (pinfunction "7_7") (pintype "passive"))
      (node (ref "LED5") (pin "2") (pinfunction "2_2") (pintype "passive"))
      (node (ref "P1") (pin "7") (pinfunction "7_7") (pintype "passive"))
      (node (ref "P1") (pin "8") (pinfunction "8_8") (pintype "passive"))
      (node (ref "R1") (pin "1") (pinfunction "1_1") (pintype "passive"))
      (node (ref "R4") (pin "1") (pinfunction "1_1") (pintype "passive"))
      (node (ref "R5") (pin "1") (pinfunction "1_1") (pintype "passive"))
      (node (ref "R65") (pin "2") (pinfunction "2_2") (pintype "passive"))
      (node (ref "RP3") (pin "3") (pinfunction "3_3") (pintype "passive"))
      (node (ref "RP3") (pin "4") (pinfunction "4_4") (pintype "passive"))
      (node (ref "RP4") (pin "1") (pinfunction "1_1") (pintype "passive"))
      (node (ref "RP4") (pin "2") (pinfunction "2_2") (pintype "passive"))
      (node (ref "RP4") (pin "3") (pinfunction "3_3") (pintype "passive"))
      (node (ref "RP4") (pin "4") (pinfunction "4_4") (pintype "passive"))
      (node (ref "SW2") (pin "2") (pinfunction "NO_2") (pintype "passive"))
      (node (ref "SW2") (pin "5") (pinfunction "NO_5") (pintype "passive"))
      (node (ref "U10") (pin "1") (pinfunction "A_1") (pintype "passive"))
      (node (ref "U11") (pin "23") (pinfunction "VSS_23") (pintype "passive"))
      (node (ref "U11") (pin "35") (pinfunction "VSS2_35") (pintype "passive"))
      (node (ref "U11") (pin "47") (pinfunction "VSS3_47") (pintype "passive"))
      (node (ref "U11") (pin "8") (pinfunction "VSSA_8") (pintype "passive"))
      (node (ref "U13") (pin "10") (pinfunction "CLKSEL0_10") (pintype "passive"))
      (node (ref "U13") (pin "17") (pinfunction "H_SA0/MOSI_17") (pintype "passive"))
      (node (ref "U13") (pin "2") (pinfunction "GND_2") (pintype "passive"))
      (node (ref "U13") (pin "25") (pinfunction "GNDIO_25") (pintype "passive"))
      (node (ref "U14") (pin "0") (pinfunction "SH_0") (pintype "passive"))
      (node (ref "U14") (pin "1") (pinfunction "SH_1") (pintype "passive"))
      (node (ref "U14") (pin "2") (pinfunction "SH_2") (pintype "passive"))
      (node (ref "U14") (pin "3") (pinfunction "SH_3") (pintype "passive"))
      (node (ref "U14") (pin "A1") (pinfunction "GND_A1") (pintype "passive"))
      (node (ref "U14") (pin "A12") (pinfunction "GND_A12") (pintype "passive"))
      (node (ref "U14") (pin "B1") (pinfunction "GND_B1") (pintype "passive"))
      (node (ref "U14") (pin "B12") (pinfunction "GND_B12") (pintype "passive"))
      (node (ref "U2") (pin "2") (pinfunction "GND_2") (pintype "passive"))
      (node (ref "U3") (pin "14") (pinfunction "GND_14") (pintype "passive"))
      (node (ref "U3") (pin "25") (pinfunction "EXTCLK_25") (pintype "passive"))
    )
    (net (code "96") (name "Net-(J29-Pad32)") (class "Default")
      (node (ref "J29") (pin "32") (pinfunction "32_32") (pintype "passive"))
      (node (ref "R57") (pin "2") (pinfunction "2_2") (pintype "passive"))
      (node (ref "SW2") (pin "1") (pinfunction "COMMON_1") (pintype "passive"))
      (node (ref "SW2") (pin "6") (pinfunction "COMMON_6") (pintype "passive"))
    )
    (net (code "97") (name "Net-(LED5-Pad1)") (class "Default")
      (node (ref "LED5") (pin "1") (pinfunction "1_1") (pintype "passive"))
      (node (ref "R66") (pin "1") (pinfunction "1_1") (pintype "passive"))
    )
    (net (code "98") (name "Net-(U2-VBUS)") (class "Default")
      (node (ref "R6") (pin "2") (pinfunction "2_2") (pintype "passive"))
      (node (ref "R65") (pin "1") (pinfunction "1_1") (pintype "passive"))
      (node (ref "U2") (pin "8") (pinfunction "VBUS_8") (pintype "passive"))
    )
    (net (code "99") (name "Net-(U2-~{RST})") (class "Default")
      (node (ref "R56") (pin "2") (pinfunction "2_2") (pintype "passive"))
      (node (ref "U2") (pin "9") (pinfunction "~{RST}_9") (pintype "passive"))
    )
    (net (code "100") (name "Net-(U3-#OE)") (class "Default")
      (node (ref "JP7") (pin "2") (pinfunction "B_2") (pintype "passive"))
      (node (ref "RP3") (pin "8") (pinfunction "8_8") (pintype "passive"))
      (node (ref "U3") (pin "23") (pinfunction "#OE_23") (pintype "passive"))
    )
    (net (code "101") (name "Net-(U3-A0)") (class "Default")
      (node (ref "RP3") (pin "6") (pinfunction "6_6") (pintype "passive"))
      (node (ref "U3") (pin "1") (pinfunction "A0_1") (pintype "passive"))
    )
    (net (code "102") (name "Net-(U3-A1)") (class "Default")
      (node (ref "RP3") (pin "5") (pinfunction "5_5") (pintype "passive"))
      (node (ref "U3") (pin "2") (pinfunction "A1_2") (pintype "passive"))
    )
    (net (code "103") (name "Net-(U3-A2)") (class "Default")
      (node (ref "RP4") (pin "8") (pinfunction "8_8") (pintype "passive"))
      (node (ref "U3") (pin "3") (pinfunction "A2_3") (pintype "passive"))
    )
    (net (code "104") (name "Net-(U3-A3)") (class "Default")
      (node (ref "RP4") (pin "7") (pinfunction "7_7") (pintype "passive"))
      (node (ref "U3") (pin "4") (pinfunction "A3_4") (pintype "passive"))
    )
    (net (code "105") (name "Net-(U3-A4)") (class "Default")
      (node (ref "RP4") (pin "6") (pinfunction "6_6") (pintype "passive"))
      (node (ref "U3") (pin "5") (pinfunction "A4_5") (pintype "passive"))
    )
    (net (code "106") (name "Net-(U3-A5)") (class "Default")
      (node (ref "RP4") (pin "5") (pinfunction "5_5") (pintype "passive"))
      (node (ref "U3") (pin "24") (pinfunction "A5_24") (pintype "passive"))
    )
    (net (code "107") (name "Net-(U3-SCL)") (class "Default")
      (node (ref "JP8") (pin "2") (pinfunction "B_2") (pintype "passive"))
      (node (ref "U3") (pin "26") (pinfunction "SCL_26") (pintype "passive"))
    )
    (net (code "108") (name "Net-(U3-SDA)") (class "Default")
      (node (ref "JP9") (pin "2") (pinfunction "B_2") (pintype "passive"))
      (node (ref "U3") (pin "27") (pinfunction "SDA_27") (pintype "passive"))
    )
    (net (code "109") (name "Net-(U11-BOOT0)") (class "Default")
      (node (ref "R1") (pin "2") (pinfunction "2_2") (pintype "passive"))
      (node (ref "U11") (pin "44") (pinfunction "BOOT0_44") (pintype "passive"))
    )
    (net (code "110") (name "Net-(U11-PC13)") (class "Default")
      (node (ref "R66") (pin "2") (pinfunction "2_2") (pintype "passive"))
      (node (ref "U11") (pin "2") (pinfunction "PC13_2") (pintype "passive"))
    )
    (net (code "111") (name "Net-(U13-CAP)") (class "Default")
      (node (ref "C54") (pin "1") (pinfunction "1_1") (pintype "passive"))
      (node (ref "U13") (pin "9") (pinfunction "CAP_9") (pintype "passive"))
    )
    (net (code "112") (name "Net-(U14-CC1)") (class "Default")
      (node (ref "R5") (pin "2") (pinfunction "2_2") (pintype "passive"))
      (node (ref "U14") (pin "A5") (pinfunction "CC1_A5") (pintype "passive"))
    )
    (net (code "113") (name "Net-(U14-CC2)") (class "Default")
      (node (ref "R4") (pin "2") (pinfunction "2_2") (pintype "passive"))
      (node (ref "U14") (pin "B5") (pinfunction "CC2_B5") (pintype "passive"))
    )
    (net (code "114") (name "unconnected-(J1-Pad7)") (class "Default")
      (node (ref "J1") (pin "7") (pinfunction "7_7") (pintype "passive"))
    )
    (net (code "115") (name "unconnected-(J1-Pad11)") (class "Default")
      (node (ref "J1") (pin "11") (pinfunction "11_11") (pintype "passive"))
    )
    (net (code "116") (name "unconnected-(J1-Pad12)") (class "Default")
      (node (ref "J1") (pin "12") (pinfunction "12_12") (pintype "passive"))
    )
    (net (code "117") (name "unconnected-(J1-Pad13)") (class "Default")
      (node (ref "J1") (pin "13") (pinfunction "13_13") (pintype "passive"))
    )
    (net (code "118") (name "unconnected-(J1-Pad16)") (class "Default")
      (node (ref "J1") (pin "16") (pinfunction "16_16") (pintype "passive"))
    )
    (net (code "119") (name "unconnected-(J1-Pad18)") (class "Default")
      (node (ref "J1") (pin "18") (pinfunction "18_18") (pintype "passive"))
    )
    (net (code "120") (name "unconnected-(J1-Pad19)") (class "Default")
      (node (ref "J1") (pin "19") (pinfunction "19_19") (pintype "passive"))
    )
    (net (code "121") (name "unconnected-(J1-Pad21)") (class "Default")
      (node (ref "J1") (pin "21") (pinfunction "21_21") (pintype "passive"))
    )
    (net (code "122") (name "unconnected-(J1-Pad22)") (class "Default")
      (node (ref "J1") (pin "22") (pinfunction "22_22") (pintype "passive"))
    )
    (net (code "123") (name "unconnected-(J1-Pad23)") (class "Default")
      (node (ref "J1") (pin "23") (pinfunction "23_23") (pintype "passive"))
    )
    (net (code "124") (name "unconnected-(J1-Pad24)") (class "Default")
      (node (ref "J1") (pin "24") (pinfunction "24_24") (pintype "passive"))
    )
    (net (code "125") (name "unconnected-(J1-Pad26)") (class "Default")
      (node (ref "J1") (pin "26") (pinfunction "26_26") (pintype "passive"))
    )
    (net (code "126") (name "unconnected-(J1-Pad27)") (class "Default")
      (node (ref "J1") (pin "27") (pinfunction "27_27") (pintype "passive"))
    )
    (net (code "127") (name "unconnected-(J1-Pad28)") (class "Default")
      (node (ref "J1") (pin "28") (pinfunction "28_28") (pintype "passive"))
    )
    (net (code "128") (name "unconnected-(J1-Pad29)") (class "Default")
      (node (ref "J1") (pin "29") (pinfunction "29_29") (pintype "passive"))
    )
    (net (code "129") (name "unconnected-(J1-Pad31)") (class "Default")
      (node (ref "J1") (pin "31") (pinfunction "31_31") (pintype "passive"))
    )
    (net (code "130") (name "unconnected-(J1-Pad32)") (class "Default")
      (node (ref "J1") (pin "32") (pinfunction "32_32") (pintype "passive"))
    )
    (net (code "131") (name "unconnected-(J1-Pad33)") (class "Default")
      (node (ref "J1") (pin "33") (pinfunction "33_33") (pintype "passive"))
    )
    (net (code "132") (name "unconnected-(J1-Pad35)") (class "Default")
      (node (ref "J1") (pin "35") (pinfunction "35_35") (pintype "passive"))
    )
    (net (code "133") (name "unconnected-(J1-Pad36)") (class "Default")
      (node (ref "J1") (pin "36") (pinfunction "36_36") (pintype "passive"))
    )
    (net (code "134") (name "unconnected-(J1-Pad37)") (class "Default")
      (node (ref "J1") (pin "37") (pinfunction "37_37") (pintype "passive"))
    )
    (net (code "135") (name "unconnected-(J1-Pad38)") (class "Default")
      (node (ref "J1") (pin "38") (pinfunction "38_38") (pintype "passive"))
    )
    (net (code "136") (name "unconnected-(J1-Pad40)") (class "Default")
      (node (ref "J1") (pin "40") (pinfunction "40_40") (pintype "passive"))
    )
    (net (code "137") (name "unconnected-(J28-Pad8)") (class "Default")
      (node (ref "J28") (pin "8") (pinfunction "8_8") (pintype "passive"))
    )
    (net (code "138") (name "unconnected-(J28-Pad10)") (class "Default")
      (node (ref "J28") (pin "10") (pinfunction "10_10") (pintype "passive"))
    )
    (net (code "139") (name "unconnected-(J28-Pad11)") (class "Default")
      (node (ref "J28") (pin "11") (pinfunction "11_11") (pintype "passive"))
    )
    (net (code "140") (name "unconnected-(J28-Pad12)") (class "Default")
      (node (ref "J28") (pin "12") (pinfunction "12_12") (pintype "passive"))
    )
    (net (code "141") (name "unconnected-(J28-Pad15)") (class "Default")
      (node (ref "J28") (pin "15") (pinfunction "15_15") (pintype "passive"))
    )
    (net (code "142") (name "unconnected-(J28-Pad17)") (class "Default")
      (node (ref "J28") (pin "17") (pinfunction "17_17") (pintype "passive"))
    )
    (net (code "143") (name "unconnected-(J28-Pad20)") (class "Default")
      (node (ref "J28") (pin "20") (pinfunction "20_20") (pintype "passive"))
    )
    (net (code "144") (name "unconnected-(J28-Pad21)") (class "Default")
      (node (ref "J28") (pin "21") (pinfunction "21_21") (pintype "passive"))
    )
    (net (code "145") (name "unconnected-(J28-Pad22)") (class "Default")
      (node (ref "J28") (pin "22") (pinfunction "22_22") (pintype "passive"))
    )
    (net (code "146") (name "unconnected-(J28-Pad24)") (class "Default")
      (node (ref "J28") (pin "24") (pinfunction "24_24") (pintype "passive"))
    )
    (net (code "147") (name "unconnected-(J28-Pad25)") (class "Default")
      (node (ref "J28") (pin "25") (pinfunction "25_25") (pintype "passive"))
    )
    (net (code "148") (name "unconnected-(J28-Pad29)") (class "Default")
      (node (ref "J28") (pin "29") (pinfunction "29_29") (pintype "passive"))
    )
    (net (code "149") (name "unconnected-(J28-Pad30)") (class "Default")
      (node (ref "J28") (pin "30") (pinfunction "30_30") (pintype "passive"))
    )
    (net (code "150") (name "unconnected-(J28-Pad33)") (class "Default")
      (node (ref "J28") (pin "33") (pinfunction "33_33") (pintype "passive"))
    )
    (net (code "151") (name "unconnected-(J28-Pad34)") (class "Default")
      (node (ref "J28") (pin "34") (pinfunction "34_34") (pintype "passive"))
    )
    (net (code "152") (name "unconnected-(J28-Pad35)") (class "Default")
      (node (ref "J28") (pin "35") (pinfunction "35_35") (pintype "passive"))
    )
    (net (code "153") (name "unconnected-(J28-Pad36)") (class "Default")
      (node (ref "J28") (pin "36") (pinfunction "36_36") (pintype "passive"))
    )
    (net (code "154") (name "unconnected-(J28-Pad37)") (class "Default")
      (node (ref "J28") (pin "37") (pinfunction "37_37") (pintype "passive"))
    )
    (net (code "155") (name "unconnected-(J29-Pad2)") (class "Default")
      (node (ref "J29") (pin "2") (pinfunction "2_2") (pintype "passive"))
    )
    (net (code "156") (name "unconnected-(J29-Pad3)") (class "Default")
      (node (ref "J29") (pin "3") (pinfunction "3_3") (pintype "passive"))
    )
    (net (code "157") (name "unconnected-(J29-Pad4)") (class "Default")
      (node (ref "J29") (pin "4") (pinfunction "4_4") (pintype "passive"))
    )
    (net (code "158") (name "unconnected-(J29-Pad5)") (class "Default")
      (node (ref "J29") (pin "5") (pinfunction "5_5") (pintype "passive"))
    )
    (net (code "159") (name "unconnected-(J29-Pad7)") (class "Default")
      (node (ref "J29") (pin "7") (pinfunction "7_7") (pintype "passive"))
    )
    (net (code "160") (name "unconnected-(J29-Pad8)") (class "Default")
      (node (ref "J29") (pin "8") (pinfunction "8_8") (pintype "passive"))
    )
    (net (code "161") (name "unconnected-(J29-Pad9)") (class "Default")
      (node (ref "J29") (pin "9") (pinfunction "9_9") (pintype "passive"))
    )
    (net (code "162") (name "unconnected-(J29-Pad13)") (class "Default")
      (node (ref "J29") (pin "13") (pinfunction "13_13") (pintype "passive"))
    )
    (net (code "163") (name "unconnected-(J29-Pad14)") (class "Default")
      (node (ref "J29") (pin "14") (pinfunction "14_14") (pintype "passive"))
    )
    (net (code "164") (name "unconnected-(J29-Pad22)") (class "Default")
      (node (ref "J29") (pin "22") (pinfunction "22_22") (pintype "passive"))
    )
    (net (code "165") (name "unconnected-(J29-Pad24)") (class "Default")
      (node (ref "J29") (pin "24") (pinfunction "24_24") (pintype "passive"))
    )
    (net (code "166") (name "unconnected-(J29-Pad29)") (class "Default")
      (node (ref "J29") (pin "29") (pinfunction "29_29") (pintype "passive"))
    )
    (net (code "167") (name "unconnected-(J29-Pad33)") (class "Default")
      (node (ref "J29") (pin "33") (pinfunction "33_33") (pintype "passive"))
    )
    (net (code "168") (name "unconnected-(J29-Pad34)") (class "Default")
      (node (ref "J29") (pin "34") (pinfunction "34_34") (pintype "passive"))
    )
    (net (code "169") (name "unconnected-(J29-Pad35)") (class "Default")
      (node (ref "J29") (pin "35") (pinfunction "35_35") (pintype "passive"))
    )
    (net (code "170") (name "unconnected-(J29-Pad36)") (class "Default")
      (node (ref "J29") (pin "36") (pinfunction "36_36") (pintype "passive"))
    )
    (net (code "171") (name "unconnected-(J29-Pad37)") (class "Default")
      (node (ref "J29") (pin "37") (pinfunction "37_37") (pintype "passive"))
    )
    (net (code "172") (name "unconnected-(J29-Pad38)") (class "Default")
      (node (ref "J29") (pin "38") (pinfunction "38_38") (pintype "passive"))
    )
    (net (code "173") (name "unconnected-(RP3-Pad2)") (class "Default")
      (node (ref "RP3") (pin "2") (pinfunction "2_2") (pintype "passive"))
    )
    (net (code "174") (name "unconnected-(RP3-Pad7)") (class "Default")
      (node (ref "RP3") (pin "7") (pinfunction "7_7") (pintype "passive"))
    )
    (net (code "175") (name "unconnected-(U2-CTS-Pad18)") (class "Default")
      (node (ref "U2") (pin "18") (pinfunction "CTS_18") (pintype "passive"))
    )
    (net (code "176") (name "unconnected-(U2-DCD-Pad24)") (class "Default")
      (node (ref "U2") (pin "24") (pinfunction "DCD_24") (pintype "passive"))
    )
    (net (code "177") (name "unconnected-(U2-DSR-Pad22)") (class "Default")
      (node (ref "U2") (pin "22") (pinfunction "DSR_22") (pintype "passive"))
    )
    (net (code "178") (name "unconnected-(U2-DTR-Pad23)") (class "Default")
      (node (ref "U2") (pin "23") (pinfunction "DTR_23") (pintype "passive"))
    )
    (net (code "179") (name "unconnected-(U2-GPIO.0{slash}TXT-Pad14)") (class "Default")
      (node (ref "U2") (pin "14") (pinfunction "GPIO.0/TXT_14") (pintype "passive"))
    )
    (net (code "180") (name "unconnected-(U2-GPIO.1{slash}RXT-Pad13)") (class "Default")
      (node (ref "U2") (pin "13") (pinfunction "GPIO.1/RXT_13") (pintype "passive"))
    )
    (net (code "181") (name "unconnected-(U2-GPIO.2{slash}RS485-Pad12)") (class "Default")
      (node (ref "U2") (pin "12") (pinfunction "GPIO.2/RS485_12") (pintype "passive"))
    )
    (net (code "182") (name "unconnected-(U2-GPIO.3{slash}WAKEUP-Pad11)") (class "Default")
      (node (ref "U2") (pin "11") (pinfunction "GPIO.3/WAKEUP_11") (pintype "passive"))
    )
    (net (code "183") (name "unconnected-(U2-RI{slash}CLK-Pad1)") (class "Default")
      (node (ref "U2") (pin "1") (pinfunction "RI/CLK_1") (pintype "passive"))
    )
    (net (code "184") (name "unconnected-(U2-RTS-Pad19)") (class "Default")
      (node (ref "U2") (pin "19") (pinfunction "RTS_19") (pintype "passive"))
    )
    (net (code "185") (name "unconnected-(U2-SUSPEND-Pad17)") (class "Default")
      (node (ref "U2") (pin "17") (pinfunction "SUSPEND_17") (pintype "passive"))
    )
    (net (code "186") (name "unconnected-(U2-~{SUSPEND}-Pad15)") (class "Default")
      (node (ref "U2") (pin "15") (pinfunction "~{SUSPEND}_15") (pintype "passive"))
    )
    (net (code "187") (name "unconnected-(U3-PWM2-Pad8)") (class "Default")
      (node (ref "U3") (pin "8") (pinfunction "PWM2_8") (pintype "passive"))
    )
    (net (code "188") (name "unconnected-(U3-PWM3-Pad9)") (class "Default")
      (node (ref "U3") (pin "9") (pinfunction "PWM3_9") (pintype "passive"))
    )
    (net (code "189") (name "unconnected-(U3-PWM8-Pad15)") (class "Default")
      (node (ref "U3") (pin "15") (pinfunction "PWM8_15") (pintype "passive"))
    )
    (net (code "190") (name "unconnected-(U3-PWM9-Pad16)") (class "Default")
      (node (ref "U3") (pin "16") (pinfunction "PWM9_16") (pintype "passive"))
    )
    (net (code "191") (name "unconnected-(U3-PWM10-Pad17)") (class "Default")
      (node (ref "U3") (pin "17") (pinfunction "PWM10_17") (pintype "passive"))
    )
    (net (code "192") (name "unconnected-(U3-PWM11-Pad18)") (class "Default")
      (node (ref "U3") (pin "18") (pinfunction "PWM11_18") (pintype "passive"))
    )
    (net (code "193") (name "unconnected-(U3-PWM12-Pad19)") (class "Default")
      (node (ref "U3") (pin "19") (pinfunction "PWM12_19") (pintype "passive"))
    )
    (net (code "194") (name "unconnected-(U3-PWM13-Pad20)") (class "Default")
      (node (ref "U3") (pin "20") (pinfunction "PWM13_20") (pintype "passive"))
    )
    (net (code "195") (name "unconnected-(U3-PWM14-Pad21)") (class "Default")
      (node (ref "U3") (pin "21") (pinfunction "PWM14_21") (pintype "passive"))
    )
    (net (code "196") (name "unconnected-(U3-PWM15-Pad22)") (class "Default")
      (node (ref "U3") (pin "22") (pinfunction "PWM15_22") (pintype "passive"))
    )
    (net (code "197") (name "unconnected-(U11-PA8-Pad29)") (class "Default")
      (node (ref "U11") (pin "29") (pinfunction "PA8_29") (pintype "passive"))
    )
    (net (code "198") (name "unconnected-(U11-PA11-Pad32)") (class "Default")
      (node (ref "U11") (pin "32") (pinfunction "PA11_32") (pintype "passive"))
    )
    (net (code "199") (name "unconnected-(U11-PA12-Pad33)") (class "Default")
      (node (ref "U11") (pin "33") (pinfunction "PA12_33") (pintype "passive"))
    )
    (net (code "200") (name "unconnected-(U11-PA15-Pad38)") (class "Default")
      (node (ref "U11") (pin "38") (pinfunction "PA15_38") (pintype "passive"))
    )
    (net (code "201") (name "unconnected-(U11-VBAT-Pad1)") (class "Default")
      (node (ref "U11") (pin "1") (pinfunction "VBAT_1") (pintype "passive"))
    )
    (net (code "202") (name "unconnected-(U13-H_CSN-Pad18)") (class "Default")
      (node (ref "U13") (pin "18") (pinfunction "H_CSN_18") (pintype "passive"))
    )
    (net (code "203") (name "unconnected-(U13-S_SCL-Pad15)") (class "Default")
      (node (ref "U13") (pin "15") (pinfunction "S_SCL_15") (pintype "passive"))
    )
    (net (code "204") (name "unconnected-(U13-S_SDA-Pad16)") (class "Default")
      (node (ref "U13") (pin "16") (pinfunction "S_SDA_16") (pintype "passive"))
    )
    (net (code "205") (name "unconnected-(U14-SBU1-PadA8)") (class "Default")
      (node (ref "U14") (pin "A8") (pinfunction "SBU1_A8") (pintype "passive"))
    )
    (net (code "206") (name "unconnected-(U14-SBU2-PadB8)") (class "Default")
      (node (ref "U14") (pin "B8") (pinfunction "SBU2_B8") (pintype "passive"))
    )
  )
)
